# SCH_slime-vr.net
KiCad netlist of a schematic drawn in EasyEDA
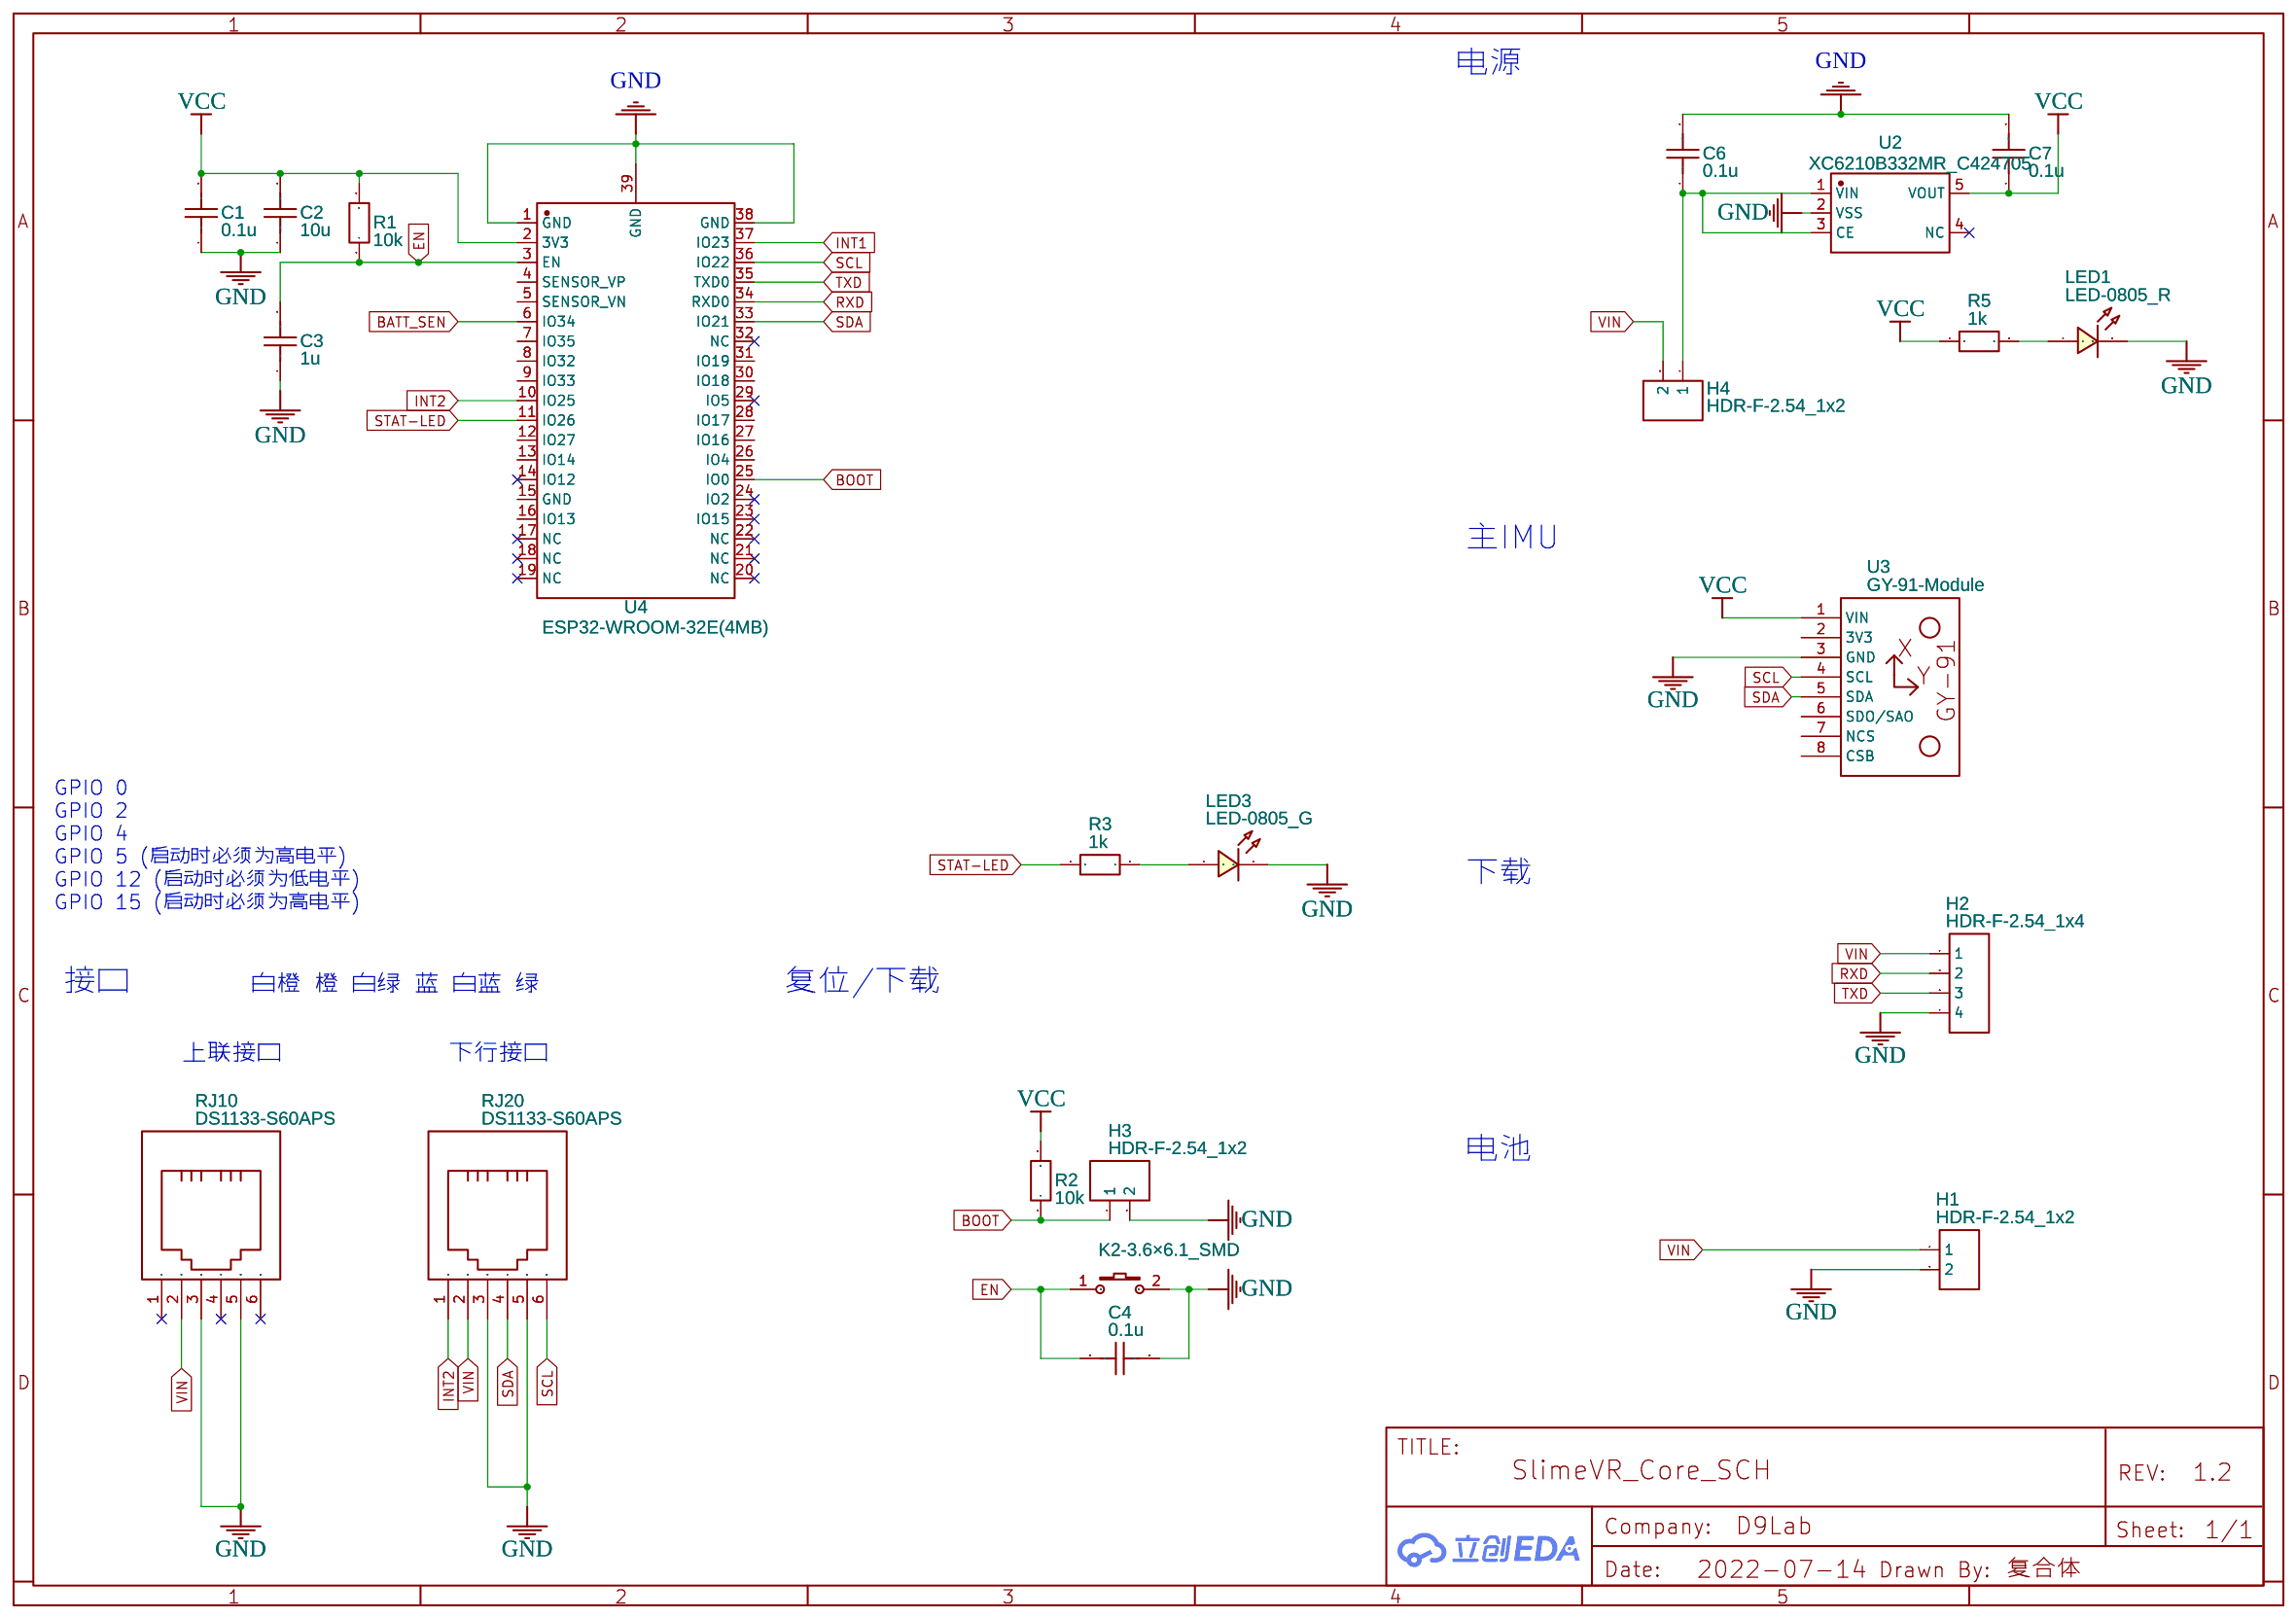
[diagram p0: SlimeVR_Core_SCH]
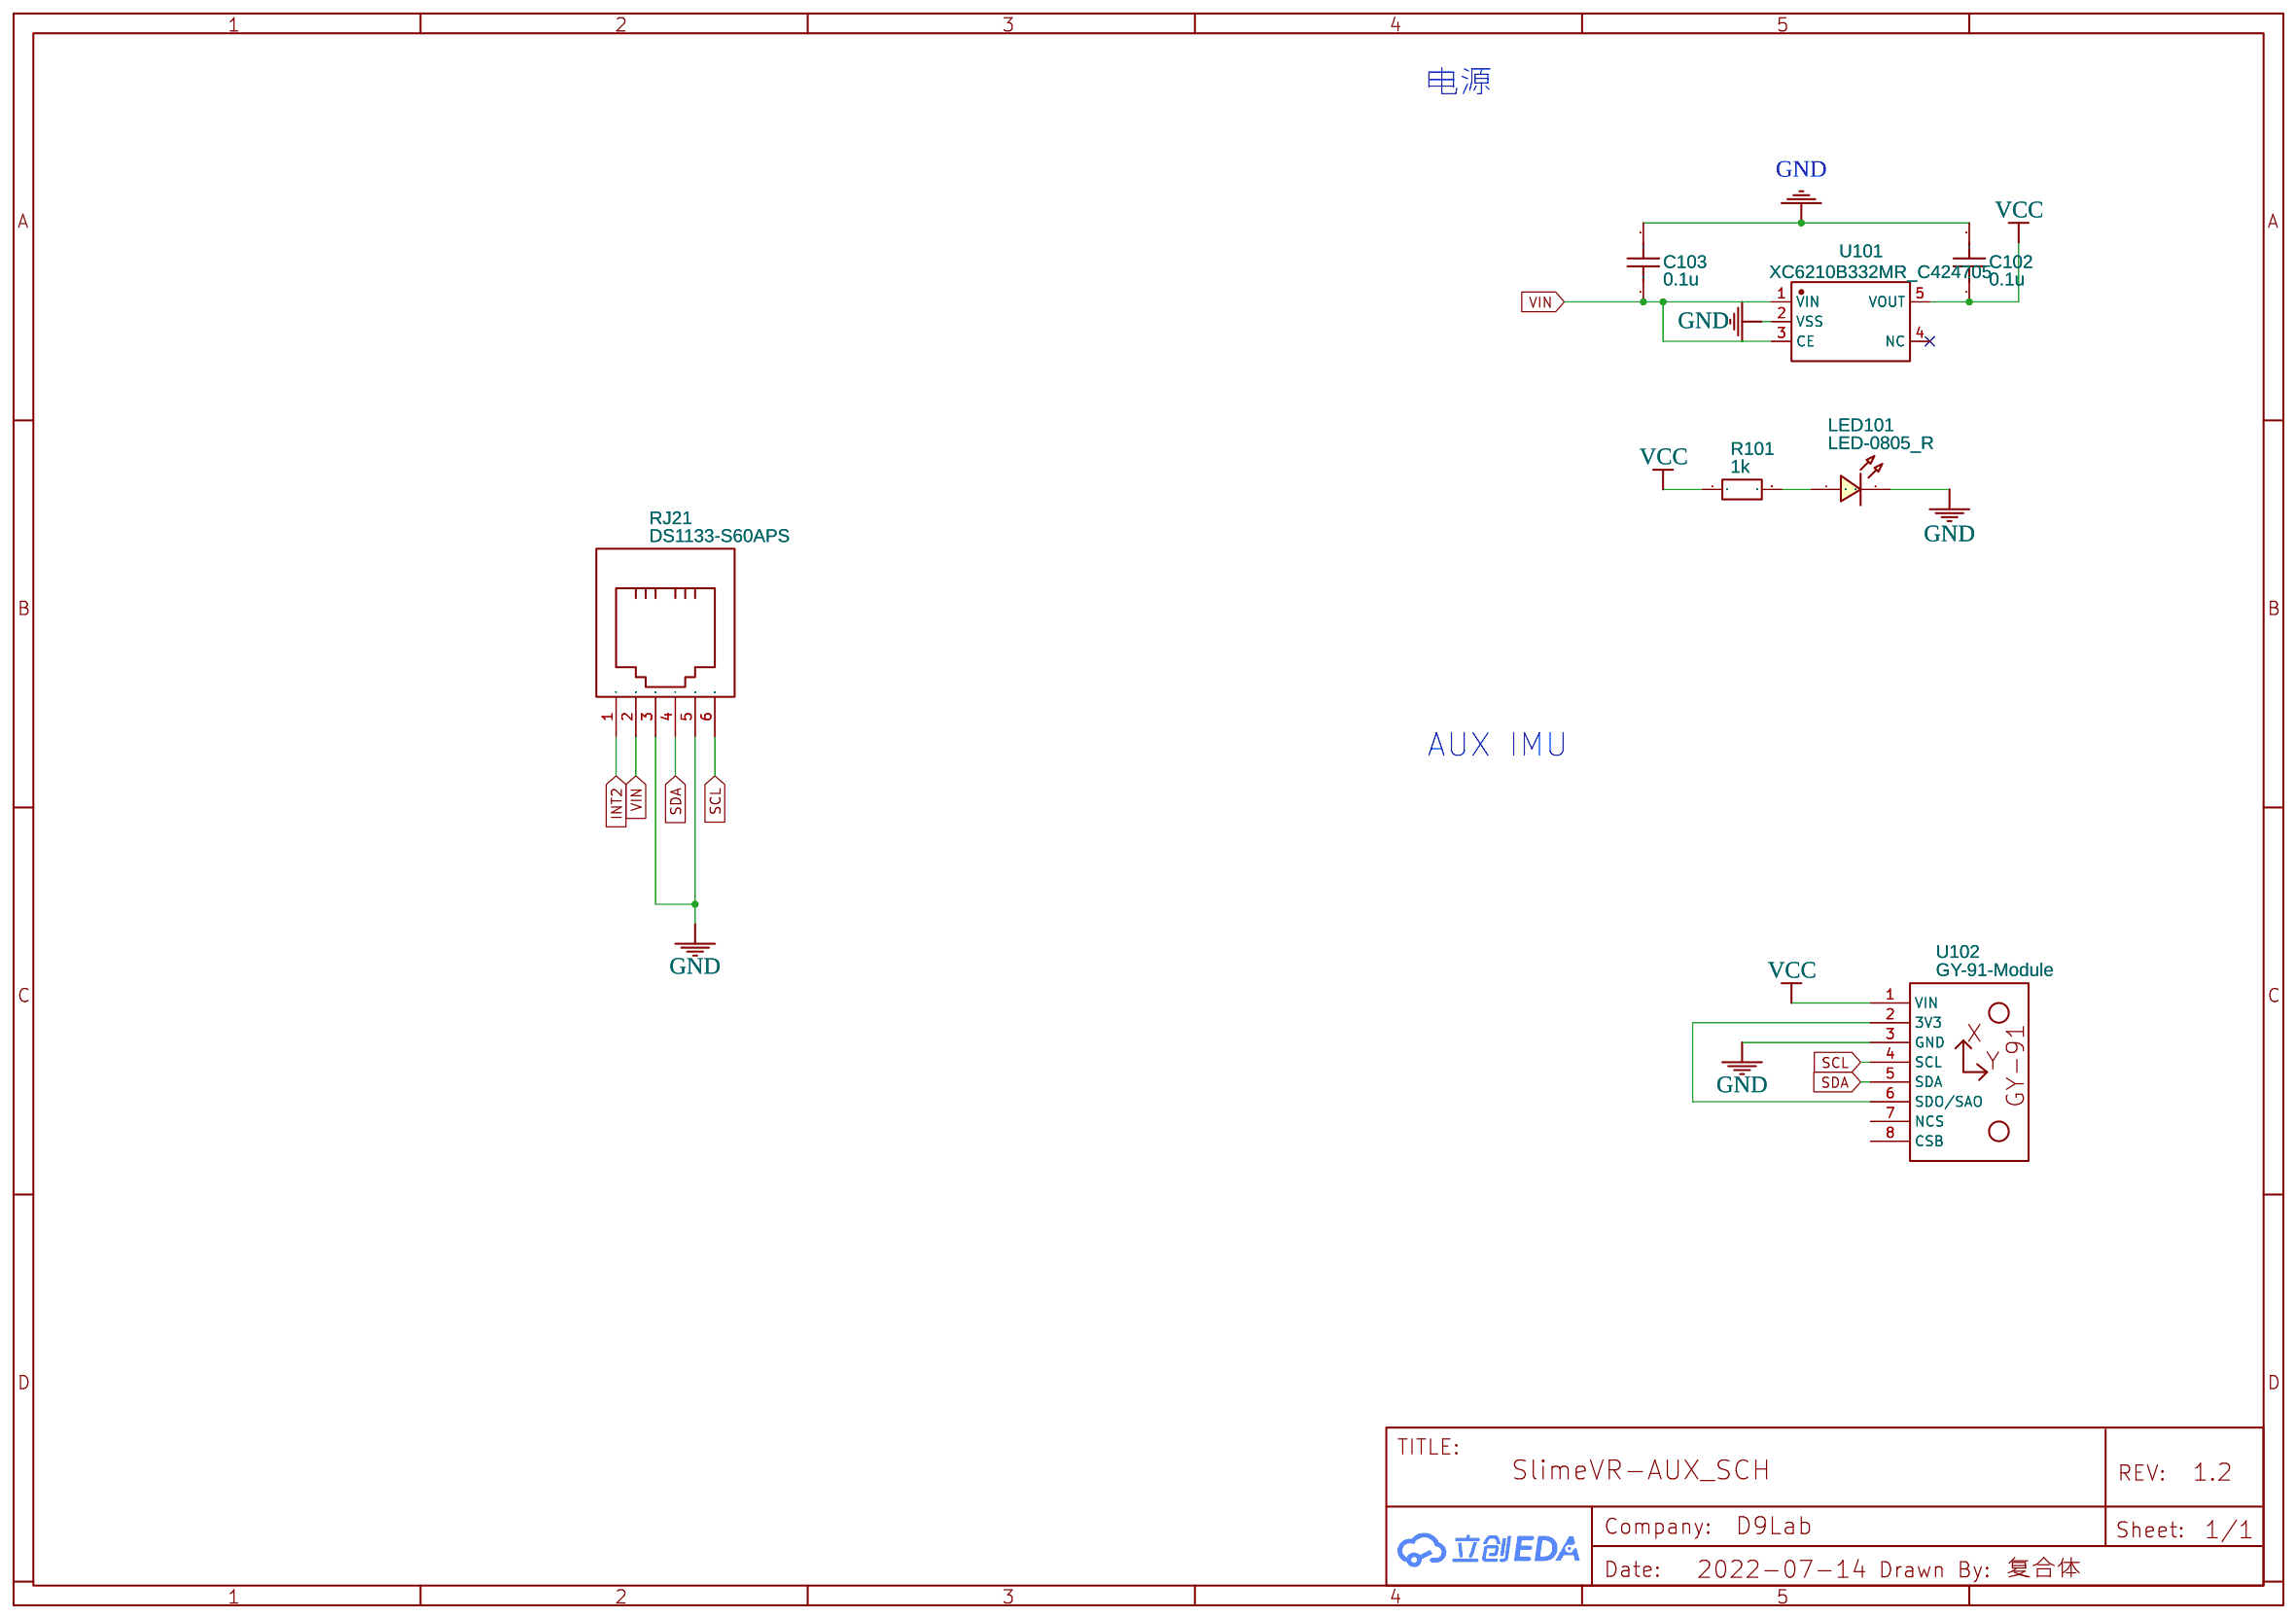
[diagram p1: SlimeVR-AUX_SCH]

(export (version "E")
  (design (tool "Eeschema 10.0.6"))
  (components
    (comp (ref "C1") (value "0.1u") (libsource (lib "") (part "C_0805_US")))
    (comp (ref "C2") (value "10u") (libsource (lib "") (part "C_0805_US")))
    (comp (ref "C3") (value "1u") (libsource (lib "") (part "C_0805_US")))
    (comp (ref "C4") (value "0.1u") (libsource (lib "") (part "C_0805_US_1")))
    (comp (ref "C6") (value "0.1u") (libsource (lib "") (part "C_0805_US")))
    (comp (ref "C7") (value "0.1u") (libsource (lib "") (part "C_0805_US")))
    (comp (ref "EN")
      (value "K2-3.6×6.1_SMD")
      (fields
        (field (name "BOM_Manufacturer Part") "K2-1107ST-A4SW-06")
        (field (name "BOM_Supplier Part") "C118141")
      )
      (libsource (lib "") (part "K2-3.6×6.1_SMD"))
    )
    (comp (ref "H1")
      (value "HDR-F-2.54_1x2")
      (fields (field (name "BOM_Supplier Part") "C49661"))
      (libsource (lib "") (part "HDR-F-2.54_1x2_1"))
    )
    (comp (ref "H2")
      (value "HDR-F-2.54_1x4")
      (fields (field (name "BOM_Supplier Part") "C225501"))
      (libsource (lib "") (part "HDR-F-2.54_1x4"))
    )
    (comp (ref "H3")
      (value "HDR-F-2.54_1x2")
      (fields (field (name "BOM_Supplier Part") "C49661"))
      (libsource (lib "") (part "HDR-F-2.54_1x2_2"))
    )
    (comp (ref "H4")
      (value "HDR-F-2.54_1x2")
      (fields (field (name "BOM_Supplier Part") "C49661"))
      (libsource (lib "") (part "HDR-F-2.54_1x2"))
    )
    (comp (ref "LED1")
      (value "LED-0805_R")
      (fields
        (field (name "BOM_Manufacturer Part") "17-21SURC/S530-A3/TR8")
        (field (name "BOM_Supplier Part") "C72037")
      )
      (libsource (lib "") (part "LED-0805_R"))
    )
    (comp (ref "LED3")
      (value "LED-0805_G")
      (fields (field (name "BOM_Manufacturer Part") "NCD0805G1") (field (name "BOM_Supplier Part") "C84260"))
      (libsource (lib "") (part "LED-0805_G"))
    )
    (comp (ref "R1") (value "10k") (libsource (lib "") (part "R_0805_EU_1")))
    (comp (ref "R2") (value "10k") (libsource (lib "") (part "R_0805_EU_1")))
    (comp (ref "R3") (value "1k") (libsource (lib "") (part "R_0805_EU")))
    (comp (ref "R5") (value "1k") (libsource (lib "") (part "R_0805_EU")))
    (comp (ref "RJ10")
      (value "DS1133-S60APS")
      (fields (field (name "BOM_Supplier Part") "C77857"))
      (libsource (lib "") (part "DS1133-S60APS"))
    )
    (comp (ref "RJ20")
      (value "DS1133-S60APS")
      (fields (field (name "BOM_Supplier Part") "C77857"))
      (libsource (lib "") (part "DS1133-S60APS"))
    )
    (comp (ref "U2")
      (value "XC6210B332MR_C424705")
      (fields
        (field (name "BOM_Manufacturer Part") "XC6210B332MR")
        (field (name "BOM_Supplier Part") "C424705")
      )
      (libsource (lib "") (part "XC6210B332MR_C424705"))
    )
    (comp (ref "U3")
      (value "GY-91-Module")
      (fields (field (name "BOM_Manufacturer Part") "GY-91 MPU9250 + BMP280"))
      (libsource (lib "") (part "GY-91-Module"))
    )
    (comp (ref "U4")
      (value "ESP32-WROOM-32E(4MB)")
      (fields (field (name "BOM_Supplier Part") "C701341"))
      (libsource (lib "") (part "ESP32-WROOM-32E(4MB)"))
    )
    (comp (ref "C102") (value "0.1u") (libsource (lib "") (part "C_0805_US")))
    (comp (ref "C103") (value "0.1u") (libsource (lib "") (part "C_0805_US")))
    (comp (ref "LED101")
      (value "LED-0805_R")
      (fields
        (field (name "BOM_Manufacturer Part") "17-21SURC/S530-A3/TR8")
        (field (name "BOM_Supplier Part") "C72037")
      )
      (libsource (lib "") (part "LED-0805_R"))
    )
    (comp (ref "R101") (value "1k") (libsource (lib "") (part "R_0805_EU")))
    (comp (ref "RJ21")
      (value "DS1133-S60APS")
      (fields (field (name "BOM_Supplier Part") "C77857"))
      (libsource (lib "") (part "DS1133-S60APS"))
    )
    (comp (ref "U101")
      (value "XC6210B332MR_C424705")
      (fields
        (field (name "BOM_Manufacturer Part") "XC6210B332MR")
        (field (name "BOM_Supplier Part") "C424705")
      )
      (libsource (lib "") (part "XC6210B332MR_C424705"))
    )
    (comp (ref "U102")
      (value "GY-91-Module")
      (fields (field (name "BOM_Manufacturer Part") "GY-91 MPU9250 + BMP280"))
      (libsource (lib "") (part "GY-91-Module"))
    )
  )
  (nets
    (net (code "1") (name "BATT_SEN") (class "Default")
      (node (ref "U4") (pin "6") (pinfunction "IO34_6") (pintype "unspecified"))
    )
    (net (code "2") (name "BOOT") (class "Default")
      (node (ref "H3") (pin "1") (pinfunction "1_1") (pintype "input"))
      (node (ref "R2") (pin "1") (pinfunction "1_1") (pintype "unspecified"))
      (node (ref "U4") (pin "25") (pinfunction "IO0_25") (pintype "unspecified"))
    )
    (net (code "3") (name "EN") (class "Default")
      (node (ref "C3") (pin "2") (pinfunction "2_2") (pintype "unspecified"))
      (node (ref "C4") (pin "2") (pinfunction "2_2") (pintype "unspecified"))
      (node (ref "EN") (pin "1") (pinfunction "1_1") (pintype "unspecified"))
      (node (ref "R1") (pin "1") (pinfunction "1_1") (pintype "unspecified"))
      (node (ref "U4") (pin "3") (pinfunction "EN_3") (pintype "unspecified"))
    )
    (net (code "4") (name "GND") (class "Default")
      (node (ref "C1") (pin "1") (pinfunction "1_1") (pintype "unspecified"))
      (node (ref "C102") (pin "2") (pinfunction "2_2") (pintype "unspecified"))
      (node (ref "C103") (pin "2") (pinfunction "2_2") (pintype "unspecified"))
      (node (ref "C2") (pin "1") (pinfunction "1_1") (pintype "unspecified"))
      (node (ref "C3") (pin "1") (pinfunction "1_1") (pintype "unspecified"))
      (node (ref "C4") (pin "1") (pinfunction "1_1") (pintype "unspecified"))
      (node (ref "C6") (pin "2") (pinfunction "2_2") (pintype "unspecified"))
      (node (ref "C7") (pin "2") (pinfunction "2_2") (pintype "unspecified"))
      (node (ref "EN") (pin "2") (pinfunction "2_2") (pintype "unspecified"))
      (node (ref "H1") (pin "2") (pinfunction "2_2") (pintype "input"))
      (node (ref "H2") (pin "4") (pinfunction "4_4") (pintype "unspecified"))
      (node (ref "H3") (pin "2") (pinfunction "2_2") (pintype "input"))
      (node (ref "LED1") (pin "2") (pinfunction "2_2") (pintype "unspecified"))
      (node (ref "LED101") (pin "2") (pinfunction "2_2") (pintype "unspecified"))
      (node (ref "LED3") (pin "2") (pinfunction "2_2") (pintype "unspecified"))
      (node (ref "RJ10") (pin "3") (pinfunction "3_3") (pintype "unspecified"))
      (node (ref "RJ10") (pin "5") (pinfunction "5_5") (pintype "unspecified"))
      (node (ref "RJ20") (pin "3") (pinfunction "3_3") (pintype "unspecified"))
      (node (ref "RJ20") (pin "5") (pinfunction "5_5") (pintype "unspecified"))
      (node (ref "RJ21") (pin "3") (pinfunction "3_3") (pintype "unspecified"))
      (node (ref "RJ21") (pin "5") (pinfunction "5_5") (pintype "unspecified"))
      (node (ref "U101") (pin "2") (pinfunction "VSS_2") (pintype "unspecified"))
      (node (ref "U102") (pin "3") (pinfunction "GND_3") (pintype "unspecified"))
      (node (ref "U2") (pin "2") (pinfunction "VSS_2") (pintype "unspecified"))
      (node (ref "U3") (pin "3") (pinfunction "GND_3") (pintype "unspecified"))
      (node (ref "U4") (pin "1") (pinfunction "GND_1") (pintype "unspecified"))
      (node (ref "U4") (pin "38") (pinfunction "GND_38") (pintype "unspecified"))
      (node (ref "U4") (pin "39") (pinfunction "GND_39") (pintype "unspecified"))
    )
    (net (code "5") (name "INT1") (class "Default")
      (node (ref "U4") (pin "37") (pinfunction "IO23_37") (pintype "unspecified"))
    )
    (net (code "6") (name "INT2") (class "Default")
      (node (ref "RJ20") (pin "1") (pinfunction "1_1") (pintype "unspecified"))
      (node (ref "RJ21") (pin "1") (pinfunction "1_1") (pintype "unspecified"))
      (node (ref "U4") (pin "10") (pinfunction "IO25_10") (pintype "unspecified"))
    )
    (net (code "7") (name "Net-(LED1-Pad1)") (class "Default")
      (node (ref "LED1") (pin "1") (pinfunction "1_1") (pintype "unspecified"))
      (node (ref "R5") (pin "2") (pinfunction "2_2") (pintype "unspecified"))
    )
    (net (code "8") (name "Net-(LED3-Pad1)") (class "Default")
      (node (ref "LED3") (pin "1") (pinfunction "1_1") (pintype "unspecified"))
      (node (ref "R3") (pin "2") (pinfunction "2_2") (pintype "unspecified"))
    )
    (net (code "9") (name "Net-(LED101-Pad1)") (class "Default")
      (node (ref "LED101") (pin "1") (pinfunction "1_1") (pintype "unspecified"))
      (node (ref "R101") (pin "2") (pinfunction "2_2") (pintype "unspecified"))
    )
    (net (code "10") (name "Net-(U2-CE)") (class "Default")
      (node (ref "C6") (pin "1") (pinfunction "1_1") (pintype "unspecified"))
      (node (ref "H4") (pin "1") (pinfunction "1_1") (pintype "input"))
      (node (ref "U2") (pin "1") (pinfunction "VIN_1") (pintype "unspecified"))
      (node (ref "U2") (pin "3") (pinfunction "CE_3") (pintype "unspecified"))
    )
    (net (code "11") (name "Net-(U102-3V3)") (class "Default")
      (node (ref "U102") (pin "2") (pinfunction "3V3_2") (pintype "unspecified"))
      (node (ref "U102") (pin "6") (pinfunction "SDO/SAO_6") (pintype "unspecified"))
    )
    (net (code "12") (name "RXD") (class "Default")
      (node (ref "H2") (pin "2") (pinfunction "2_2") (pintype "unspecified"))
      (node (ref "U4") (pin "34") (pinfunction "RXD0_34") (pintype "unspecified"))
    )
    (net (code "13") (name "SCL") (class "Default")
      (node (ref "RJ20") (pin "6") (pinfunction "6_6") (pintype "unspecified"))
      (node (ref "RJ21") (pin "6") (pinfunction "6_6") (pintype "unspecified"))
      (node (ref "U102") (pin "4") (pinfunction "SCL_4") (pintype "unspecified"))
      (node (ref "U3") (pin "4") (pinfunction "SCL_4") (pintype "unspecified"))
      (node (ref "U4") (pin "36") (pinfunction "IO22_36") (pintype "unspecified"))
    )
    (net (code "14") (name "SDA") (class "Default")
      (node (ref "RJ20") (pin "4") (pinfunction "4_4") (pintype "unspecified"))
      (node (ref "RJ21") (pin "4") (pinfunction "4_4") (pintype "unspecified"))
      (node (ref "U102") (pin "5") (pinfunction "SDA_5") (pintype "unspecified"))
      (node (ref "U3") (pin "5") (pinfunction "SDA_5") (pintype "unspecified"))
      (node (ref "U4") (pin "33") (pinfunction "IO21_33") (pintype "unspecified"))
    )
    (net (code "15") (name "STAT-LED") (class "Default")
      (node (ref "R3") (pin "1") (pinfunction "1_1") (pintype "unspecified"))
      (node (ref "U4") (pin "11") (pinfunction "IO26_11") (pintype "unspecified"))
    )
    (net (code "16") (name "TXD") (class "Default")
      (node (ref "H2") (pin "3") (pinfunction "3_3") (pintype "unspecified"))
      (node (ref "U4") (pin "35") (pinfunction "TXD0_35") (pintype "unspecified"))
    )
    (net (code "17") (name "VCC") (class "Default")
      (node (ref "C1") (pin "2") (pinfunction "2_2") (pintype "unspecified"))
      (node (ref "C102") (pin "1") (pinfunction "1_1") (pintype "unspecified"))
      (node (ref "C2") (pin "2") (pinfunction "2_2") (pintype "unspecified"))
      (node (ref "C7") (pin "1") (pinfunction "1_1") (pintype "unspecified"))
      (node (ref "R1") (pin "2") (pinfunction "2_2") (pintype "unspecified"))
      (node (ref "R101") (pin "1") (pinfunction "1_1") (pintype "unspecified"))
      (node (ref "R2") (pin "2") (pinfunction "2_2") (pintype "unspecified"))
      (node (ref "R5") (pin "1") (pinfunction "1_1") (pintype "unspecified"))
      (node (ref "U101") (pin "5") (pinfunction "VOUT_5") (pintype "unspecified"))
      (node (ref "U102") (pin "1") (pinfunction "VIN_1") (pintype "unspecified"))
      (node (ref "U2") (pin "5") (pinfunction "VOUT_5") (pintype "unspecified"))
      (node (ref "U3") (pin "1") (pinfunction "VIN_1") (pintype "unspecified"))
      (node (ref "U4") (pin "2") (pinfunction "3V3_2") (pintype "unspecified"))
    )
    (net (code "18") (name "VIN") (class "Default")
      (node (ref "C103") (pin "1") (pinfunction "1_1") (pintype "unspecified"))
      (node (ref "H1") (pin "1") (pinfunction "1_1") (pintype "input"))
      (node (ref "H2") (pin "1") (pinfunction "1_1") (pintype "unspecified"))
      (node (ref "H4") (pin "2") (pinfunction "2_2") (pintype "input"))
      (node (ref "RJ10") (pin "2") (pinfunction "2_2") (pintype "unspecified"))
      (node (ref "RJ20") (pin "2") (pinfunction "2_2") (pintype "unspecified"))
      (node (ref "RJ21") (pin "2") (pinfunction "2_2") (pintype "unspecified"))
      (node (ref "U101") (pin "1") (pinfunction "VIN_1") (pintype "unspecified"))
      (node (ref "U101") (pin "3") (pinfunction "CE_3") (pintype "unspecified"))
    )
    (net (code "19") (name "unconnected-(RJ10-Pad1)") (class "Default")
      (node (ref "RJ10") (pin "1") (pinfunction "1_1") (pintype "unspecified+no_connect"))
    )
    (net (code "20") (name "unconnected-(RJ10-Pad4)") (class "Default")
      (node (ref "RJ10") (pin "4") (pinfunction "4_4") (pintype "unspecified+no_connect"))
    )
    (net (code "21") (name "unconnected-(RJ10-Pad6)") (class "Default")
      (node (ref "RJ10") (pin "6") (pinfunction "6_6") (pintype "unspecified+no_connect"))
    )
    (net (code "22") (name "unconnected-(U2-NC-Pad4)") (class "Default")
      (node (ref "U2") (pin "4") (pinfunction "NC_4") (pintype "unspecified+no_connect"))
    )
    (net (code "23") (name "unconnected-(U3-3V3-Pad2)") (class "Default")
      (node (ref "U3") (pin "2") (pinfunction "3V3_2") (pintype "unspecified"))
    )
    (net (code "24") (name "unconnected-(U3-CSB-Pad8)") (class "Default")
      (node (ref "U3") (pin "8") (pinfunction "CSB_8") (pintype "unspecified"))
    )
    (net (code "25") (name "unconnected-(U3-NCS-Pad7)") (class "Default")
      (node (ref "U3") (pin "7") (pinfunction "NCS_7") (pintype "unspecified"))
    )
    (net (code "26") (name "unconnected-(U3-SDO{slash}SAO-Pad6)") (class "Default")
      (node (ref "U3") (pin "6") (pinfunction "SDO/SAO_6") (pintype "unspecified"))
    )
    (net (code "27") (name "unconnected-(U4-GND-Pad15)") (class "Default")
      (node (ref "U4") (pin "15") (pinfunction "GND_15") (pintype "unspecified"))
    )
    (net (code "28") (name "unconnected-(U4-IO2-Pad24)") (class "Default")
      (node (ref "U4") (pin "24") (pinfunction "IO2_24") (pintype "unspecified+no_connect"))
    )
    (net (code "29") (name "unconnected-(U4-IO4-Pad26)") (class "Default")
      (node (ref "U4") (pin "26") (pinfunction "IO4_26") (pintype "unspecified"))
    )
    (net (code "30") (name "unconnected-(U4-IO5-Pad29)") (class "Default")
      (node (ref "U4") (pin "29") (pinfunction "IO5_29") (pintype "unspecified+no_connect"))
    )
    (net (code "31") (name "unconnected-(U4-IO12-Pad14)") (class "Default")
      (node (ref "U4") (pin "14") (pinfunction "IO12_14") (pintype "unspecified+no_connect"))
    )
    (net (code "32") (name "unconnected-(U4-IO13-Pad16)") (class "Default")
      (node (ref "U4") (pin "16") (pinfunction "IO13_16") (pintype "unspecified"))
    )
    (net (code "33") (name "unconnected-(U4-IO14-Pad13)") (class "Default")
      (node (ref "U4") (pin "13") (pinfunction "IO14_13") (pintype "unspecified"))
    )
    (net (code "34") (name "unconnected-(U4-IO15-Pad23)") (class "Default")
      (node (ref "U4") (pin "23") (pinfunction "IO15_23") (pintype "unspecified+no_connect"))
    )
    (net (code "35") (name "unconnected-(U4-IO16-Pad27)") (class "Default")
      (node (ref "U4") (pin "27") (pinfunction "IO16_27") (pintype "unspecified"))
    )
    (net (code "36") (name "unconnected-(U4-IO17-Pad28)") (class "Default")
      (node (ref "U4") (pin "28") (pinfunction "IO17_28") (pintype "unspecified"))
    )
    (net (code "37") (name "unconnected-(U4-IO18-Pad30)") (class "Default")
      (node (ref "U4") (pin "30") (pinfunction "IO18_30") (pintype "unspecified"))
    )
    (net (code "38") (name "unconnected-(U4-IO19-Pad31)") (class "Default")
      (node (ref "U4") (pin "31") (pinfunction "IO19_31") (pintype "unspecified"))
    )
    (net (code "39") (name "unconnected-(U4-IO27-Pad12)") (class "Default")
      (node (ref "U4") (pin "12") (pinfunction "IO27_12") (pintype "unspecified"))
    )
    (net (code "40") (name "unconnected-(U4-IO32-Pad8)") (class "Default")
      (node (ref "U4") (pin "8") (pinfunction "IO32_8") (pintype "unspecified"))
    )
    (net (code "41") (name "unconnected-(U4-IO33-Pad9)") (class "Default")
      (node (ref "U4") (pin "9") (pinfunction "IO33_9") (pintype "unspecified"))
    )
    (net (code "42") (name "unconnected-(U4-IO35-Pad7)") (class "Default")
      (node (ref "U4") (pin "7") (pinfunction "IO35_7") (pintype "unspecified"))
    )
    (net (code "43") (name "unconnected-(U4-NC-Pad17)") (class "Default")
      (node (ref "U4") (pin "17") (pinfunction "NC_17") (pintype "unspecified+no_connect"))
    )
    (net (code "44") (name "unconnected-(U4-NC-Pad18)") (class "Default")
      (node (ref "U4") (pin "18") (pinfunction "NC_18") (pintype "unspecified+no_connect"))
    )
    (net (code "45") (name "unconnected-(U4-NC-Pad19)") (class "Default")
      (node (ref "U4") (pin "19") (pinfunction "NC_19") (pintype "unspecified+no_connect"))
    )
    (net (code "46") (name "unconnected-(U4-NC-Pad20)") (class "Default")
      (node (ref "U4") (pin "20") (pinfunction "NC_20") (pintype "unspecified+no_connect"))
    )
    (net (code "47") (name "unconnected-(U4-NC-Pad21)") (class "Default")
      (node (ref "U4") (pin "21") (pinfunction "NC_21") (pintype "unspecified+no_connect"))
    )
    (net (code "48") (name "unconnected-(U4-NC-Pad22)") (class "Default")
      (node (ref "U4") (pin "22") (pinfunction "NC_22") (pintype "unspecified+no_connect"))
    )
    (net (code "49") (name "unconnected-(U4-NC-Pad32)") (class "Default")
      (node (ref "U4") (pin "32") (pinfunction "NC_32") (pintype "unspecified+no_connect"))
    )
    (net (code "50") (name "unconnected-(U4-SENSOR_VN-Pad5)") (class "Default")
      (node (ref "U4") (pin "5") (pinfunction "SENSOR_VN_5") (pintype "unspecified"))
    )
    (net (code "51") (name "unconnected-(U4-SENSOR_VP-Pad4)") (class "Default")
      (node (ref "U4") (pin "4") (pinfunction "SENSOR_VP_4") (pintype "unspecified"))
    )
    (net (code "52") (name "unconnected-(U101-NC-Pad4)") (class "Default")
      (node (ref "U101") (pin "4") (pinfunction "NC_4") (pintype "unspecified+no_connect"))
    )
    (net (code "53") (name "unconnected-(U102-CSB-Pad8)") (class "Default")
      (node (ref "U102") (pin "8") (pinfunction "CSB_8") (pintype "unspecified"))
    )
    (net (code "54") (name "unconnected-(U102-NCS-Pad7)") (class "Default")
      (node (ref "U102") (pin "7") (pinfunction "NCS_7") (pintype "unspecified"))
    )
  )
)
